# pc_healthypi_move_nRF5340_v4.net
KiCad netlist of a schematic drawn in EAGLE
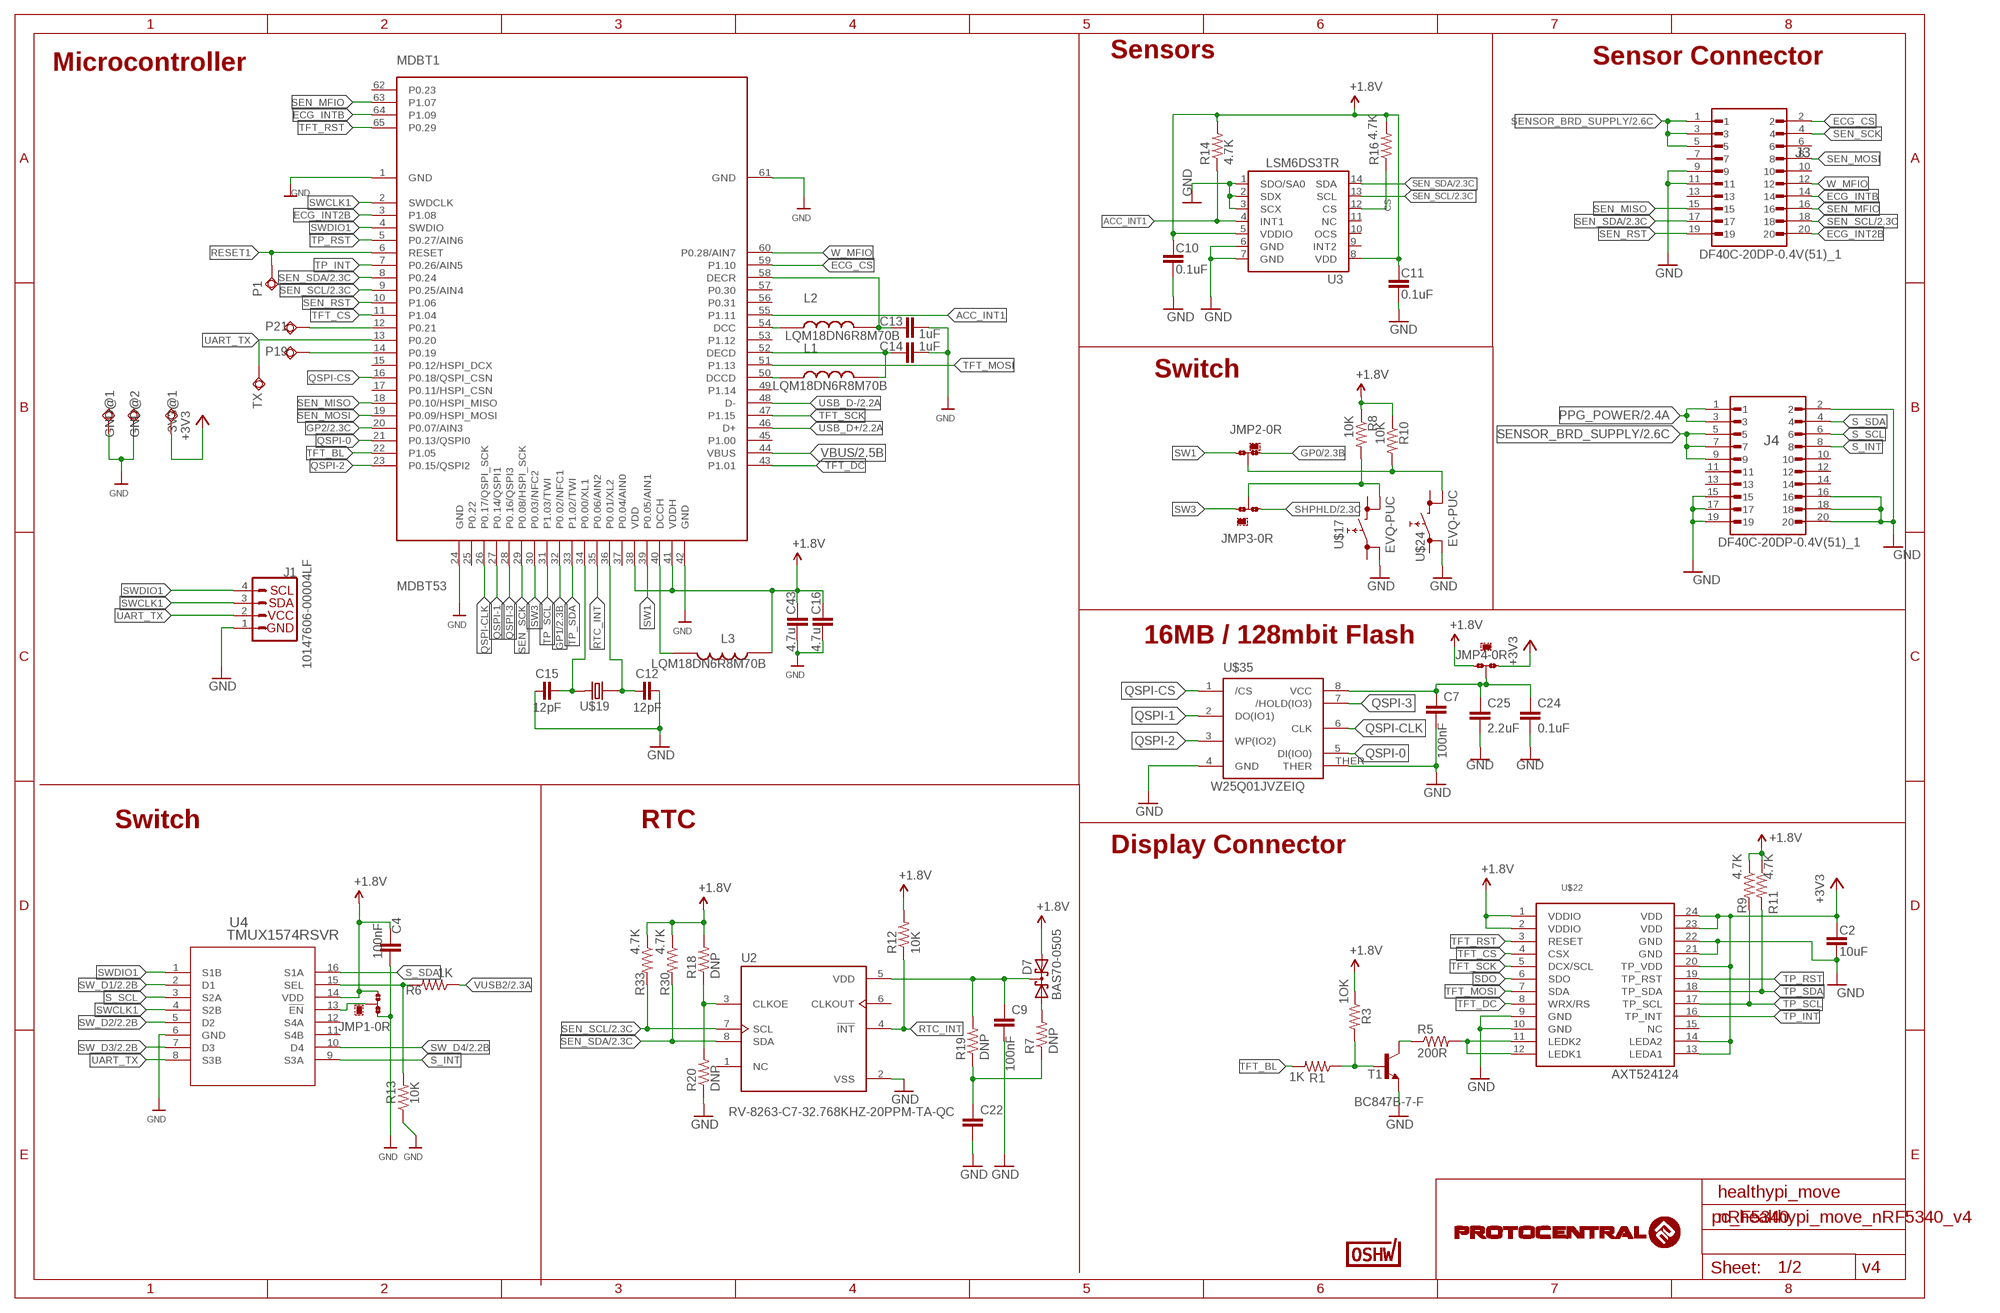
[diagram p0: schematic, sheet 1]
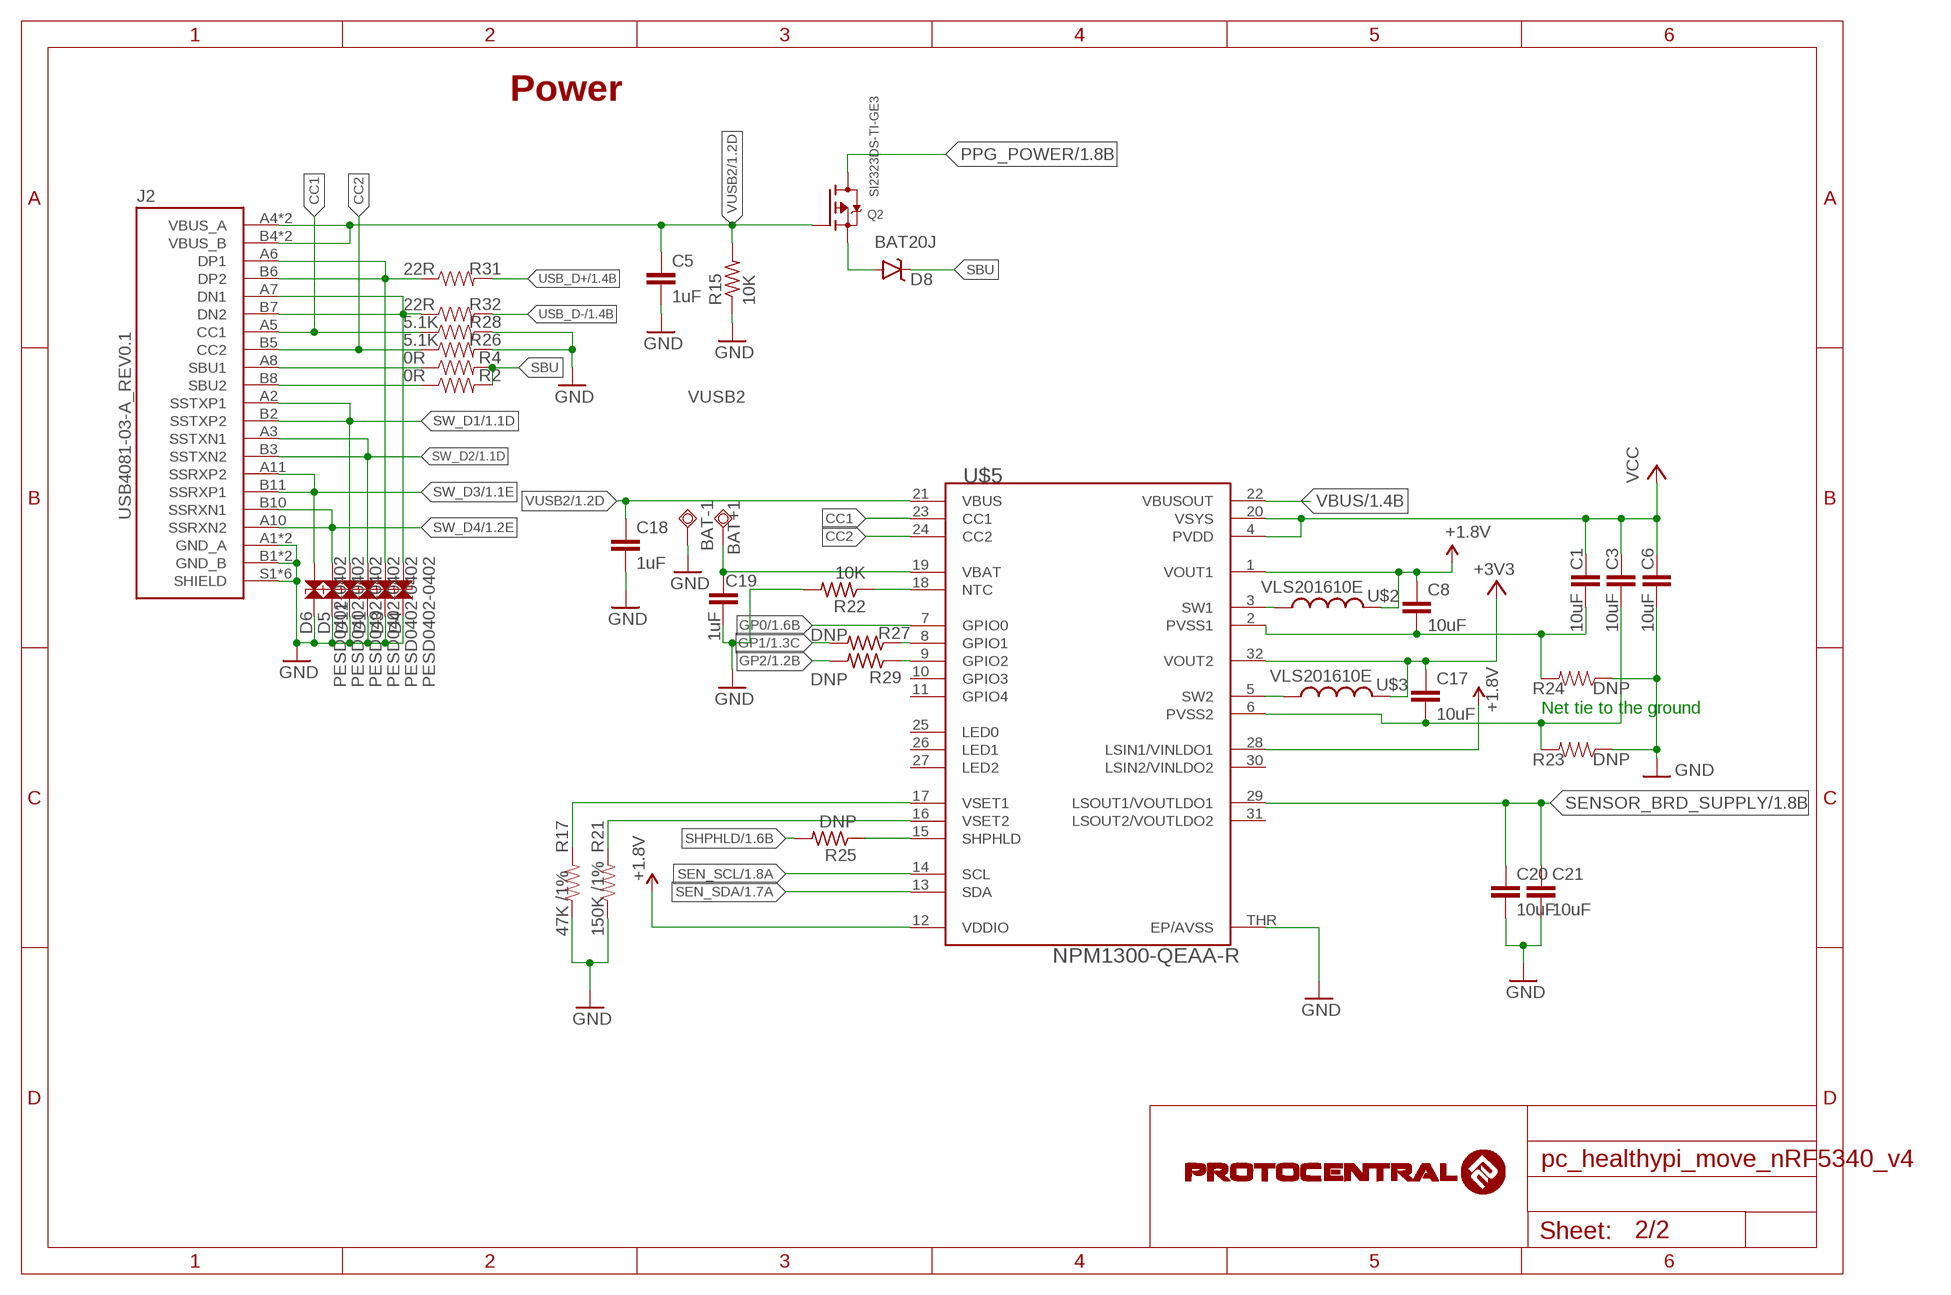
[diagram p1: schematic, sheet 2]

(export (version "E")
  (design (tool "Eeschema 10.0.6"))
  (components
    (comp (ref "BAT+1")
      (value "TPSQTP13SQ")
      (footprint "eagle-import:TP13SQ")
      (libsource (lib "eagle-import") (part "TPSQTP13SQ"))
    )
    (comp (ref "BAT-1")
      (value "TPSQTP13SQ")
      (footprint "eagle-import:TP13SQ")
      (libsource (lib "eagle-import") (part "TPSQTP13SQ"))
    )
    (comp (ref "C1")
      (value "10uF")
      (footprint "eagle-import:0402-TIGHT")
      (libsource (lib "eagle-import") (part "2.2UF-0402_TIGHT-10V-10%-X5R"))
    )
    (comp (ref "C3")
      (value "10uF")
      (footprint "eagle-import:0402-TIGHT")
      (libsource (lib "eagle-import") (part "2.2UF-0402_TIGHT-10V-10%-X5R"))
    )
    (comp (ref "C5")
      (value "1uF")
      (footprint "eagle-import:0402-TIGHT")
      (libsource (lib "eagle-import") (part "2.2UF-0402_TIGHT-10V-10%-X5R"))
    )
    (comp (ref "C6")
      (value "10uF")
      (footprint "eagle-import:0402-TIGHT")
      (libsource (lib "eagle-import") (part "2.2UF-0402_TIGHT-10V-10%-X5R"))
    )
    (comp (ref "C8")
      (value "10uF")
      (footprint "eagle-import:0402-TIGHT")
      (libsource (lib "eagle-import") (part "2.2UF-0402_TIGHT-10V-10%-X5R"))
    )
    (comp (ref "C17")
      (value "10uF")
      (footprint "eagle-import:0402-TIGHT")
      (libsource (lib "eagle-import") (part "2.2UF-0402_TIGHT-10V-10%-X5R"))
    )
    (comp (ref "C18")
      (value "1uF")
      (footprint "eagle-import:0402-TIGHT")
      (libsource (lib "eagle-import") (part "2.2UF-0402_TIGHT-10V-10%-X5R"))
    )
    (comp (ref "C19")
      (value "1uF")
      (footprint "eagle-import:0402-TIGHT")
      (libsource (lib "eagle-import") (part "2.2UF-0402_TIGHT-10V-10%-X5R"))
    )
    (comp (ref "C20")
      (value "10uF")
      (footprint "eagle-import:0402-TIGHT")
      (libsource (lib "eagle-import") (part "2.2UF-0402_TIGHT-10V-10%-X5R"))
    )
    (comp (ref "C21")
      (value "10uF")
      (footprint "eagle-import:0402-TIGHT")
      (libsource (lib "eagle-import") (part "2.2UF-0402_TIGHT-10V-10%-X5R"))
    )
    (comp (ref "D1")
      (value "PESD0402-0402")
      (footprint "eagle-import:0402")
      (fields
        (field (name "DIGIKEY_PART") "PESD0402-140CT-ND")
        (field (name "MOUSE_PART") "650-PESD0402-140")
      )
      (libsource (lib "eagle-import") (part "PESD0402-0402"))
    )
    (comp (ref "D3")
      (value "PESD0402-0402")
      (footprint "eagle-import:0402")
      (fields
        (field (name "DIGIKEY_PART") "PESD0402-140CT-ND")
        (field (name "MOUSE_PART") "650-PESD0402-140")
      )
      (libsource (lib "eagle-import") (part "PESD0402-0402"))
    )
    (comp (ref "D4")
      (value "PESD0402-0402")
      (footprint "eagle-import:0402")
      (fields
        (field (name "DIGIKEY_PART") "PESD0402-140CT-ND")
        (field (name "MOUSE_PART") "650-PESD0402-140")
      )
      (libsource (lib "eagle-import") (part "PESD0402-0402"))
    )
    (comp (ref "D5")
      (value "PESD0402-0402")
      (footprint "eagle-import:0402")
      (fields
        (field (name "DIGIKEY_PART") "PESD0402-140CT-ND")
        (field (name "MOUSE_PART") "650-PESD0402-140")
      )
      (libsource (lib "eagle-import") (part "PESD0402-0402"))
    )
    (comp (ref "D6")
      (value "PESD0402-0402")
      (footprint "eagle-import:0402")
      (fields
        (field (name "DIGIKEY_PART") "PESD0402-140CT-ND")
        (field (name "MOUSE_PART") "650-PESD0402-140")
      )
      (libsource (lib "eagle-import") (part "PESD0402-0402"))
    )
    (comp (ref "D8")
      (value "BAT20J")
      (footprint "eagle-import:SOD-323")
      (libsource (lib "eagle-import") (part "DIODE-SCHOTTKY-BAT20J"))
    )
    (comp (ref "D11")
      (value "PESD0402-0402")
      (footprint "eagle-import:0402")
      (fields
        (field (name "DIGIKEY_PART") "PESD0402-140CT-ND")
        (field (name "MOUSE_PART") "650-PESD0402-140")
      )
      (libsource (lib "eagle-import") (part "PESD0402-0402"))
    )
    (comp (ref "J2")
      (value "USB4081-03-A_REV0.1")
      (footprint "eagle-import:GCT_USB4081-03-A_REV0.1")
      (fields (field (name "MF") "Global Connector Technology") (field (name "MP") "USB4081-03-A"))
      (libsource (lib "eagle-import") (part "USB4081-03-A_REV0.1"))
    )
    (comp (ref "Q2")
      (value "SI2323DS-TI-GE3")
      (footprint "eagle-import:SOT23-R")
      (libsource (lib "eagle-import") (part "MOSFET-P"))
    )
    (comp (ref "R2")
      (value "0R")
      (footprint "eagle-import:0402-RES")
      (libsource (lib "eagle-import") (part "RESISTOR0402-RES"))
    )
    (comp (ref "R4")
      (value "0R")
      (footprint "eagle-import:0402-RES")
      (libsource (lib "eagle-import") (part "RESISTOR0402-RES"))
    )
    (comp (ref "R15")
      (value "10K")
      (footprint "eagle-import:R0402")
      (libsource (lib "eagle-import") (part "R-US_R0402"))
    )
    (comp (ref "R17")
      (value "47K /1%")
      (footprint "eagle-import:0402-RES")
      (libsource (lib "eagle-import") (part "RESISTOR0402-RES"))
    )
    (comp (ref "R21")
      (value "150K /1%")
      (footprint "eagle-import:0402-RES")
      (libsource (lib "eagle-import") (part "RESISTOR0402-RES"))
    )
    (comp (ref "R22")
      (value "10K")
      (footprint "eagle-import:R0402")
      (libsource (lib "eagle-import") (part "R-US_R0402"))
    )
    (comp (ref "R23")
      (value "DNP")
      (footprint "eagle-import:0402-RES")
      (libsource (lib "eagle-import") (part "RESISTOR0402-RES"))
    )
    (comp (ref "R24")
      (value "DNP")
      (footprint "eagle-import:0402-RES")
      (libsource (lib "eagle-import") (part "RESISTOR0402-RES"))
    )
    (comp (ref "R25")
      (value "DNP")
      (footprint "eagle-import:R0402")
      (libsource (lib "eagle-import") (part "R-US_R0402"))
    )
    (comp (ref "R26")
      (value "5.1K")
      (footprint "eagle-import:0402-RES")
      (libsource (lib "eagle-import") (part "RESISTOR0402-RES"))
    )
    (comp (ref "R27")
      (value "DNP")
      (footprint "eagle-import:R0402")
      (libsource (lib "eagle-import") (part "R-US_R0402"))
    )
    (comp (ref "R28")
      (value "5.1K")
      (footprint "eagle-import:0402-RES")
      (libsource (lib "eagle-import") (part "RESISTOR0402-RES"))
    )
    (comp (ref "R29")
      (value "DNP")
      (footprint "eagle-import:R0402")
      (libsource (lib "eagle-import") (part "R-US_R0402"))
    )
    (comp (ref "R31")
      (value "22R")
      (footprint "eagle-import:0402-RES")
      (libsource (lib "eagle-import") (part "RESISTOR0402-RES"))
    )
    (comp (ref "R32")
      (value "22R")
      (footprint "eagle-import:0402-RES")
      (libsource (lib "eagle-import") (part "RESISTOR0402-RES"))
    )
    (comp (ref "U$2")
      (value "VLS201610E")
      (footprint "eagle-import:VLS201610E")
      (libsource (lib "eagle-import") (part "VLS201610E"))
    )
    (comp (ref "U$3")
      (value "VLS201610E")
      (footprint "eagle-import:VLS201610E")
      (libsource (lib "eagle-import") (part "VLS201610E"))
    )
    (comp (ref "U$5")
      (value "NPM1300-QEAA-R")
      (footprint "eagle-import:PWQFN-32")
      (libsource (lib "eagle-import") (part "NPM1300-QEAA-R"))
    )
    (comp (ref "3V3@1")
      (value "TPSQTP13SQ")
      (footprint "eagle-import:TP13SQ")
      (libsource (lib "eagle-import") (part "TPSQTP13SQ"))
    )
    (comp (ref "C2")
      (value "10uF")
      (footprint "eagle-import:0603@1")
      (libsource (lib "eagle-import") (part "0.1UF-0603-100V-10%"))
    )
    (comp (ref "C4")
      (value "100nF")
      (footprint "eagle-import:0402-TIGHT")
      (libsource (lib "eagle-import") (part "2.2UF-0402_TIGHT-10V-10%-X5R"))
    )
    (comp (ref "C7")
      (value "100nF")
      (footprint "eagle-import:C0402")
      (libsource (lib "eagle-import") (part "C-EUC0402"))
    )
    (comp (ref "C9")
      (value "100nF")
      (footprint "eagle-import:C0402")
      (libsource (lib "eagle-import") (part "C-EUC0402"))
    )
    (comp (ref "C10")
      (value "0.1uF")
      (footprint "eagle-import:0402-TIGHT")
      (libsource (lib "eagle-import") (part "0.1UF-0402T-6.3V-10%-X7R"))
    )
    (comp (ref "C11")
      (value "0.1uF")
      (footprint "eagle-import:0402-TIGHT")
      (libsource (lib "eagle-import") (part "0.1UF-0402T-6.3V-10%-X7R"))
    )
    (comp (ref "C12")
      (value "12pF")
      (footprint "eagle-import:C0402")
      (libsource (lib "eagle-import") (part "CAPACITORS-0402"))
    )
    (comp (ref "C13")
      (value "1uF")
      (footprint "eagle-import:0402-TIGHT")
      (libsource (lib "eagle-import") (part "2.2UF-0402_TIGHT-10V-10%-X5R"))
    )
    (comp (ref "C14")
      (value "1uF")
      (footprint "eagle-import:0402-TIGHT")
      (libsource (lib "eagle-import") (part "2.2UF-0402_TIGHT-10V-10%-X5R"))
    )
    (comp (ref "C15")
      (value "12pF")
      (footprint "eagle-import:C0402")
      (libsource (lib "eagle-import") (part "CAPACITORS-0402"))
    )
    (comp (ref "C16")
      (value "4.7u")
      (footprint "eagle-import:C0402")
      (libsource (lib "eagle-import") (part "C-EUC0402"))
    )
    (comp (ref "C22")
      (value "C-EUC1210")
      (footprint "eagle-import:C1210")
      (libsource (lib "eagle-import") (part "C-EUC1210"))
    )
    (comp (ref "C24")
      (value "0.1uF")
      (footprint "eagle-import:0402-TIGHT")
      (libsource (lib "eagle-import") (part "0.1UF-0402T-6.3V-10%-X7R"))
    )
    (comp (ref "C25")
      (value "2.2uF")
      (footprint "eagle-import:0402-TIGHT")
      (libsource (lib "eagle-import") (part "2.2UF-0402_TIGHT-10V-10%-X5R"))
    )
    (comp (ref "C43")
      (value "4.7u")
      (footprint "eagle-import:C0402")
      (libsource (lib "eagle-import") (part "C-EUC0402"))
    )
    (comp (ref "D7")
      (value "BAS70-0505")
      (footprint "eagle-import:SOT23")
      (fields (field (name "MF") "Diotec") (field (name "MP") "BAS70-05"))
      (libsource (lib "eagle-import") (part "BAS70-0505"))
    )
    (comp (ref "GND@1")
      (value "TPSQTP13SQ")
      (footprint "eagle-import:TP13SQ")
      (libsource (lib "eagle-import") (part "TPSQTP13SQ"))
    )
    (comp (ref "GND@2")
      (value "TPSQTP13SQ")
      (footprint "eagle-import:TP13SQ")
      (libsource (lib "eagle-import") (part "TPSQTP13SQ"))
    )
    (comp (ref "J1")
      (value "10147606-00004LF")
      (footprint "eagle-import:JST04_1MM_RA")
      (libsource (lib "eagle-import") (part "QWIIC_CONNECTORJS-1MM"))
    )
    (comp (ref "J3")
      (value "DF40C-20DP-0.4V(51)_1")
      (footprint "eagle-import:HRS_DF40C-20DP-0.4V(51)")
      (fields (field (name "MANUFACTURER") "Hirose Electric"))
      (libsource (lib "eagle-import") (part "DF40C-20DP-0.4V(51)_1"))
    )
    (comp (ref "J4")
      (value "DF40C-20DP-0.4V(51)_1")
      (footprint "eagle-import:HRS_DF40C-20DP-0.4V(51)")
      (fields (field (name "MANUFACTURER") "Hirose Electric"))
      (libsource (lib "eagle-import") (part "DF40C-20DP-0.4V(51)_1"))
    )
    (comp (ref "JMP1")
      (value "0R-JUMPB")
      (footprint "eagle-import:B0R-JMP")
      (libsource (lib "eagle-import") (part "0R-JUMPB"))
    )
    (comp (ref "JMP2")
      (value "0R-JUMPB")
      (footprint "eagle-import:B0R-JMP")
      (libsource (lib "eagle-import") (part "0R-JUMPB"))
    )
    (comp (ref "JMP3")
      (value "0R-JUMPB")
      (footprint "eagle-import:B0R-JMP")
      (libsource (lib "eagle-import") (part "0R-JUMPB"))
    )
    (comp (ref "JMP4")
      (value "0R-JUMPB")
      (footprint "eagle-import:B0R-JMP")
      (libsource (lib "eagle-import") (part "0R-JUMPB"))
    )
    (comp (ref "L1")
      (value "LQM18DN6R8M70B")
      (footprint "eagle-import:INDC1608X95N")
      (fields (field (name "MF") "Murata"))
      (libsource (lib "eagle-import") (part "LQM18DN6R8M70B"))
    )
    (comp (ref "L2")
      (value "LQM18DN6R8M70B")
      (footprint "eagle-import:INDC1608X95N")
      (fields (field (name "MF") "Murata"))
      (libsource (lib "eagle-import") (part "LQM18DN6R8M70B"))
    )
    (comp (ref "L3")
      (value "LQM18DN6R8M70B")
      (footprint "eagle-import:INDC1608X95N")
      (fields (field (name "MF") "Murata"))
      (libsource (lib "eagle-import") (part "LQM18DN6R8M70B"))
    )
    (comp (ref "MDBT1")
      (value "MDBT53")
      (footprint "eagle-import:MDBT53")
      (libsource (lib "eagle-import") (part "MDBT53"))
    )
    (comp (ref "P1")
      (value "TPSQTP13SQ")
      (footprint "eagle-import:TP13SQ")
      (libsource (lib "eagle-import") (part "TPSQTP13SQ"))
    )
    (comp (ref "P19")
      (value "TPSQTP13SQ")
      (footprint "eagle-import:TP13SQ")
      (libsource (lib "eagle-import") (part "TPSQTP13SQ"))
    )
    (comp (ref "P21")
      (value "TPSQTP13SQ")
      (footprint "eagle-import:TP13SQ")
      (libsource (lib "eagle-import") (part "TPSQTP13SQ"))
    )
    (comp (ref "R1")
      (value "200")
      (footprint "eagle-import:R0402")
      (libsource (lib "eagle-import") (part "R-US_R0402"))
    )
    (comp (ref "R3")
      (value "200")
      (footprint "eagle-import:R0402")
      (libsource (lib "eagle-import") (part "R-US_R0402"))
    )
    (comp (ref "R5")
      (value "200R")
      (footprint "eagle-import:R0402")
      (libsource (lib "eagle-import") (part "R-US_R0402"))
    )
    (comp (ref "R6")
      (value "1K")
      (footprint "eagle-import:0402-RES")
      (libsource (lib "eagle-import") (part "RESISTOR0402-RES"))
    )
    (comp (ref "R7")
      (value "DNP")
      (footprint "eagle-import:R0402")
      (libsource (lib "eagle-import") (part "R-US_R0402"))
    )
    (comp (ref "R8")
      (value "10K")
      (footprint "eagle-import:R0402")
      (libsource (lib "eagle-import") (part "R-US_R0402"))
    )
    (comp (ref "R9")
      (value "4.7K")
      (footprint "eagle-import:R0402")
      (libsource (lib "eagle-import") (part "R-US_R0402"))
    )
    (comp (ref "R10")
      (value "10K")
      (footprint "eagle-import:R0402")
      (libsource (lib "eagle-import") (part "R-US_R0402"))
    )
    (comp (ref "R11")
      (value "4.7K")
      (footprint "eagle-import:R0402")
      (libsource (lib "eagle-import") (part "R-US_R0402"))
    )
    (comp (ref "R12")
      (value "10K")
      (footprint "eagle-import:R0402")
      (libsource (lib "eagle-import") (part "R-US_R0402"))
    )
    (comp (ref "R13")
      (value "10K")
      (footprint "eagle-import:R0402")
      (libsource (lib "eagle-import") (part "R-US_R0402"))
    )
    (comp (ref "R14")
      (value "4.7K")
      (footprint "eagle-import:R0402")
      (libsource (lib "eagle-import") (part "R-US_R0402"))
    )
    (comp (ref "R16")
      (value "4.7K")
      (footprint "eagle-import:R0402")
      (libsource (lib "eagle-import") (part "R-US_R0402"))
    )
    (comp (ref "R18")
      (value "DNP")
      (footprint "eagle-import:R0402")
      (libsource (lib "eagle-import") (part "R-US_R0402"))
    )
    (comp (ref "R19")
      (value "DNP")
      (footprint "eagle-import:R0402")
      (libsource (lib "eagle-import") (part "R-US_R0402"))
    )
    (comp (ref "R20")
      (value "DNP")
      (footprint "eagle-import:R0402")
      (libsource (lib "eagle-import") (part "R-US_R0402"))
    )
    (comp (ref "R30")
      (value "4.7K")
      (footprint "eagle-import:R0402")
      (libsource (lib "eagle-import") (part "R-US_R0402"))
    )
    (comp (ref "R33")
      (value "4.7K")
      (footprint "eagle-import:R0402")
      (libsource (lib "eagle-import") (part "R-US_R0402"))
    )
    (comp (ref "T1")
      (value "BC847B-7-F")
      (footprint "eagle-import:SOT23-BEC")
      (libsource (lib "eagle-import") (part "-NPN-SOT23-BECMMBT2222ALT1"))
    )
    (comp (ref "TX")
      (value "TPSQTP13SQ")
      (footprint "eagle-import:TP13SQ")
      (libsource (lib "eagle-import") (part "TPSQTP13SQ"))
    )
    (comp (ref "U$1")
      (value "CERT-SMALL")
      (footprint "eagle-import:CERT-SMALL-SILK")
      (libsource (lib "eagle-import") (part "CERT-SMALL"))
    )
    (comp (ref "U$17")
      (value "EVQ-PUC")
      (footprint "eagle-import:EVQ-PUC")
      (libsource (lib "eagle-import") (part "EVQ-PUC"))
    )
    (comp (ref "U$19")
      (value "520-327-12.5-34B(32.768KHZ)")
      (footprint "eagle-import:ECX-31B")
      (libsource (lib "eagle-import") (part "ECS-X-34B"))
    )
    (comp (ref "U$22")
      (value "AXT524124")
      (footprint "eagle-import:AXT524124")
      (libsource (lib "eagle-import") (part "AXT524124"))
    )
    (comp (ref "U$24")
      (value "EVQ-PUC")
      (footprint "eagle-import:EVQ-PUC")
      (libsource (lib "eagle-import") (part "EVQ-PUC"))
    )
    (comp (ref "U$35")
      (value "W25Q01JVZEIQ")
      (footprint "eagle-import:WSON-08")
      (libsource (lib "eagle-import") (part "W25N01GVZEIG"))
    )
    (comp (ref "U2")
      (value "RV-8263-C7-32.768KHZ-20PPM-TA-QC")
      (footprint "eagle-import:IC_RV-8263-C7-32.768KHZ-20PPM-TA-QC")
      (fields (field (name "MF") "Micro Crystal"))
      (libsource (lib "eagle-import") (part "RV-8263-C7-32.768KHZ-20PPM-TA-QC"))
    )
    (comp (ref "U3")
      (value "LSM6DS3TR")
      (footprint "eagle-import:LGA14L")
      (libsource (lib "eagle-import") (part "LSM6DS3"))
    )
    (comp (ref "U4")
      (value "TMUX1574RSVR")
      (footprint "eagle-import:RSV16_TEX")
      (fields (field (name "COPYRIGHT") "Copyright (C) 2024 Ultra Librarian. All rights reserved."))
      (libsource (lib "eagle-import") (part "TMUX1574RSVR"))
    )
  )
  (nets
    (net (code "1") (name "+1.8V") (class "Default")
      (node (ref "C10") (pin "1") (pinfunction "1_1") (pintype "passive"))
      (node (ref "C11") (pin "1") (pinfunction "1_1") (pintype "passive"))
      (node (ref "C16") (pin "1") (pinfunction "1_1") (pintype "passive"))
      (node (ref "C4") (pin "1") (pinfunction "1_1") (pintype "passive"))
      (node (ref "C43") (pin "1") (pinfunction "1_1") (pintype "passive"))
      (node (ref "C8") (pin "1") (pinfunction "1_1") (pintype "passive"))
      (node (ref "D7") (pin "2") (pinfunction "A2_2") (pintype "passive"))
      (node (ref "JMP1") (pin "3") (pinfunction "3_3") (pintype "passive"))
      (node (ref "JMP4") (pin "3") (pinfunction "3_3") (pintype "passive"))
      (node (ref "L3") (pin "1") (pinfunction "1_1") (pintype "passive"))
      (node (ref "MDBT1") (pin "38") (pinfunction "VDD_38") (pintype "bidirectional"))
      (node (ref "MDBT1") (pin "41") (pinfunction "VDDH_41") (pintype "bidirectional"))
      (node (ref "R10") (pin "1") (pinfunction "1_1") (pintype "passive"))
      (node (ref "R11") (pin "1") (pinfunction "1_1") (pintype "passive"))
      (node (ref "R12") (pin "2") (pinfunction "2_2") (pintype "passive"))
      (node (ref "R14") (pin "2") (pinfunction "2_2") (pintype "passive"))
      (node (ref "R16") (pin "2") (pinfunction "2_2") (pintype "passive"))
      (node (ref "R18") (pin "2") (pinfunction "2_2") (pintype "passive"))
      (node (ref "R3") (pin "1") (pinfunction "1_1") (pintype "passive"))
      (node (ref "R30") (pin "1") (pinfunction "1_1") (pintype "passive"))
      (node (ref "R33") (pin "1") (pinfunction "1_1") (pintype "passive"))
      (node (ref "R8") (pin "1") (pinfunction "1_1") (pintype "passive"))
      (node (ref "R9") (pin "1") (pinfunction "1_1") (pintype "passive"))
      (node (ref "U$2") (pin "2") (pinfunction "2_2") (pintype "passive"))
      (node (ref "U$22") (pin "1") (pinfunction "VDDIO_1") (pintype "bidirectional"))
      (node (ref "U$22") (pin "2") (pinfunction "VDDIO_2") (pintype "bidirectional"))
      (node (ref "U$5") (pin "1") (pinfunction "VOUT1_1") (pintype "bidirectional"))
      (node (ref "U$5") (pin "12") (pinfunction "VDDIO_12") (pintype "bidirectional"))
      (node (ref "U$5") (pin "28") (pinfunction "LSIN1/VINLDO1_28") (pintype "bidirectional"))
      (node (ref "U3") (pin "5") (pinfunction "VDDIO_5") (pintype "bidirectional"))
      (node (ref "U3") (pin "8") (pinfunction "VDD_8") (pintype "bidirectional"))
      (node (ref "U4") (pin "14") (pinfunction "VDD_14") (pintype "power_in"))
    )
    (net (code "2") (name "+3V3") (class "Default")
      (node (ref "3V3@1") (pin "TP") (pinfunction "TP_TP") (pintype "input"))
      (node (ref "C17") (pin "1") (pinfunction "1_1") (pintype "passive"))
      (node (ref "C2") (pin "1") (pinfunction "1_1") (pintype "passive"))
      (node (ref "JMP4") (pin "1") (pinfunction "1_1") (pintype "passive"))
      (node (ref "U$22") (pin "13") (pinfunction "LEDA1_13") (pintype "bidirectional"))
      (node (ref "U$22") (pin "14") (pinfunction "LEDA2_14") (pintype "bidirectional"))
      (node (ref "U$22") (pin "20") (pinfunction "TP_VDD_20") (pintype "bidirectional"))
      (node (ref "U$22") (pin "23") (pinfunction "VDD_23") (pintype "bidirectional"))
      (node (ref "U$22") (pin "24") (pinfunction "VDD_24") (pintype "bidirectional"))
      (node (ref "U$3") (pin "2") (pinfunction "2_2") (pintype "passive"))
      (node (ref "U$5") (pin "32") (pinfunction "VOUT2_32") (pintype "bidirectional"))
    )
    (net (code "3") (name "ACC_INT1") (class "Default")
      (node (ref "MDBT1") (pin "55") (pinfunction "P1.11_55") (pintype "bidirectional"))
      (node (ref "R14") (pin "1") (pinfunction "1_1") (pintype "passive"))
      (node (ref "U3") (pin "4") (pinfunction "INT1_4") (pintype "bidirectional"))
    )
    (net (code "4") (name "CC1") (class "Default")
      (node (ref "J2") (pin "A5") (pinfunction "CC1_A5") (pintype "bidirectional"))
      (node (ref "R28") (pin "1") (pinfunction "1_1") (pintype "passive"))
      (node (ref "U$5") (pin "23") (pinfunction "CC1_23") (pintype "bidirectional"))
    )
    (net (code "5") (name "CC2") (class "Default")
      (node (ref "J2") (pin "B5") (pinfunction "CC2_B5") (pintype "bidirectional"))
      (node (ref "R26") (pin "1") (pinfunction "1_1") (pintype "passive"))
      (node (ref "U$5") (pin "24") (pinfunction "CC2_24") (pintype "bidirectional"))
    )
    (net (code "6") (name "CS") (class "Default")
      (node (ref "R16") (pin "1") (pinfunction "1_1") (pintype "passive"))
      (node (ref "U3") (pin "12") (pinfunction "CS_12") (pintype "bidirectional"))
    )
    (net (code "7") (name "ECG_CS") (class "Default")
      (node (ref "J3") (pin "2") (pinfunction "2_2") (pintype "passive"))
      (node (ref "MDBT1") (pin "59") (pinfunction "P1.10_59") (pintype "bidirectional"))
    )
    (net (code "8") (name "ECG_INT2B") (class "Default")
      (node (ref "J3") (pin "20") (pinfunction "20_20") (pintype "passive"))
      (node (ref "MDBT1") (pin "3") (pinfunction "P1.08_3") (pintype "bidirectional"))
    )
    (net (code "9") (name "ECG_INTB") (class "Default")
      (node (ref "J3") (pin "14") (pinfunction "14_14") (pintype "passive"))
      (node (ref "MDBT1") (pin "64") (pinfunction "P1.09_64") (pintype "bidirectional"))
    )
    (net (code "10") (name "GND") (class "Default")
      (node (ref "BAT-1") (pin "TP") (pinfunction "TP_TP") (pintype "input"))
      (node (ref "C10") (pin "2") (pinfunction "2_2") (pintype "passive"))
      (node (ref "C11") (pin "2") (pinfunction "2_2") (pintype "passive"))
      (node (ref "C12") (pin "2") (pinfunction "2_2") (pintype "passive"))
      (node (ref "C13") (pin "2") (pinfunction "2_2") (pintype "passive"))
      (node (ref "C14") (pin "2") (pinfunction "2_2") (pintype "passive"))
      (node (ref "C15") (pin "1") (pinfunction "1_1") (pintype "passive"))
      (node (ref "C16") (pin "2") (pinfunction "2_2") (pintype "passive"))
      (node (ref "C18") (pin "2") (pinfunction "2_2") (pintype "passive"))
      (node (ref "C19") (pin "2") (pinfunction "2_2") (pintype "passive"))
      (node (ref "C2") (pin "2") (pinfunction "2_2") (pintype "passive"))
      (node (ref "C20") (pin "2") (pinfunction "2_2") (pintype "passive"))
      (node (ref "C21") (pin "2") (pinfunction "2_2") (pintype "passive"))
      (node (ref "C22") (pin "2") (pinfunction "2_2") (pintype "passive"))
      (node (ref "C24") (pin "2") (pinfunction "2_2") (pintype "passive"))
      (node (ref "C25") (pin "2") (pinfunction "2_2") (pintype "passive"))
      (node (ref "C4") (pin "2") (pinfunction "2_2") (pintype "passive"))
      (node (ref "C43") (pin "2") (pinfunction "2_2") (pintype "passive"))
      (node (ref "C5") (pin "2") (pinfunction "2_2") (pintype "passive"))
      (node (ref "C6") (pin "2") (pinfunction "2_2") (pintype "passive"))
      (node (ref "C7") (pin "2") (pinfunction "2_2") (pintype "passive"))
      (node (ref "C9") (pin "2") (pinfunction "2_2") (pintype "passive"))
      (node (ref "D1") (pin "1") (pinfunction "1_1") (pintype "bidirectional"))
      (node (ref "D11") (pin "1") (pinfunction "1_1") (pintype "bidirectional"))
      (node (ref "D3") (pin "1") (pinfunction "1_1") (pintype "bidirectional"))
      (node (ref "D4") (pin "1") (pinfunction "1_1") (pintype "bidirectional"))
      (node (ref "D5") (pin "1") (pinfunction "1_1") (pintype "bidirectional"))
      (node (ref "D6") (pin "1") (pinfunction "1_1") (pintype "bidirectional"))
      (node (ref "GND@1") (pin "TP") (pinfunction "TP_TP") (pintype "input"))
      (node (ref "GND@2") (pin "TP") (pinfunction "TP_TP") (pintype "input"))
      (node (ref "J1") (pin "1") (pinfunction "1_1") (pintype "power_in"))
      (node (ref "J2") (pin "A1") (pinfunction "GND_A_A1") (pintype "power_in"))
      (node (ref "J2") (pin "A12") (pinfunction "GND_A_A12") (pintype "power_in"))
      (node (ref "J2") (pin "B1") (pinfunction "GND_B_B1") (pintype "power_in"))
      (node (ref "J2") (pin "B12") (pinfunction "GND_B_B12") (pintype "power_in"))
      (node (ref "J2") (pin "S1") (pinfunction "SHIELD_S1") (pintype "passive"))
      (node (ref "J2") (pin "S2") (pinfunction "SHIELD_S2") (pintype "passive"))
      (node (ref "J2") (pin "S3") (pinfunction "SHIELD_S3") (pintype "passive"))
      (node (ref "J2") (pin "S4") (pinfunction "SHIELD_S4") (pintype "passive"))
      (node (ref "J2") (pin "S5") (pinfunction "SHIELD_S5") (pintype "passive"))
      (node (ref "J2") (pin "S6") (pinfunction "SHIELD_S6") (pintype "passive"))
      (node (ref "J3") (pin "11") (pinfunction "11_11") (pintype "passive"))
      (node (ref "J3") (pin "9") (pinfunction "9_9") (pintype "passive"))
      (node (ref "J4") (pin "15") (pinfunction "15_15") (pintype "passive"))
      (node (ref "J4") (pin "16") (pinfunction "16_16") (pintype "passive"))
      (node (ref "J4") (pin "17") (pinfunction "17_17") (pintype "passive"))
      (node (ref "J4") (pin "18") (pinfunction "18_18") (pintype "passive"))
      (node (ref "J4") (pin "19") (pinfunction "19_19") (pintype "passive"))
      (node (ref "J4") (pin "2") (pinfunction "2_2") (pintype "passive"))
      (node (ref "J4") (pin "20") (pinfunction "20_20") (pintype "passive"))
      (node (ref "JMP1") (pin "1") (pinfunction "1_1") (pintype "passive"))
      (node (ref "MDBT1") (pin "1") (pinfunction "GND_1") (pintype "bidirectional"))
      (node (ref "MDBT1") (pin "24") (pinfunction "GND_24") (pintype "bidirectional"))
      (node (ref "MDBT1") (pin "42") (pinfunction "GND_42") (pintype "bidirectional"))
      (node (ref "MDBT1") (pin "61") (pinfunction "GND_61") (pintype "bidirectional"))
      (node (ref "R13") (pin "1") (pinfunction "1_1") (pintype "passive"))
      (node (ref "R15") (pin "1") (pinfunction "1_1") (pintype "passive"))
      (node (ref "R17") (pin "1") (pinfunction "1_1") (pintype "passive"))
      (node (ref "R20") (pin "1") (pinfunction "1_1") (pintype "passive"))
      (node (ref "R21") (pin "1") (pinfunction "1_1") (pintype "passive"))
      (node (ref "R22") (pin "2") (pinfunction "2_2") (pintype "passive"))
      (node (ref "R23") (pin "1") (pinfunction "1_1") (pintype "passive"))
      (node (ref "R24") (pin "1") (pinfunction "1_1") (pintype "passive"))
      (node (ref "R26") (pin "2") (pinfunction "2_2") (pintype "passive"))
      (node (ref "R28") (pin "2") (pinfunction "2_2") (pintype "passive"))
      (node (ref "T1") (pin "E") (pinfunction "E_E") (pintype "passive"))
      (node (ref "U$17") (pin "3") (pinfunction "0_3") (pintype "passive"))
      (node (ref "U$22") (pin "10") (pinfunction "GND_10") (pintype "bidirectional"))
      (node (ref "U$22") (pin "21") (pinfunction "GND_21") (pintype "bidirectional"))
      (node (ref "U$22") (pin "22") (pinfunction "GND_22") (pintype "bidirectional"))
      (node (ref "U$22") (pin "9") (pinfunction "GND_9") (pintype "bidirectional"))
      (node (ref "U$24") (pin "3") (pinfunction "0_3") (pintype "passive"))
      (node (ref "U$35") (pin "4") (pinfunction "GND_4") (pintype "bidirectional"))
      (node (ref "U$35") (pin "THER") (pinfunction "THER_THER") (pintype "bidirectional"))
      (node (ref "U$5") (pin "THR") (pinfunction "EP/AVSS_THR") (pintype "bidirectional"))
      (node (ref "U2") (pin "2") (pinfunction "VSS_2") (pintype "power_in"))
      (node (ref "U3") (pin "1") (pinfunction "SDO/SA0_1") (pintype "bidirectional"))
      (node (ref "U3") (pin "2") (pinfunction "SDX_2") (pintype "bidirectional"))
      (node (ref "U3") (pin "3") (pinfunction "SCX_3") (pintype "bidirectional"))
      (node (ref "U3") (pin "6") (pinfunction "GND_6") (pintype "bidirectional"))
      (node (ref "U3") (pin "7") (pinfunction "GND_7") (pintype "bidirectional"))
      (node (ref "U4") (pin "6") (pinfunction "GND_6") (pintype "passive"))
    )
    (net (code "11") (name "GP0") (class "Default")
      (node (ref "JMP2") (pin "1") (pinfunction "1_1") (pintype "passive"))
      (node (ref "U$5") (pin "7") (pinfunction "GPIO0_7") (pintype "bidirectional"))
    )
    (net (code "12") (name "GP1") (class "Default")
      (node (ref "MDBT1") (pin "32") (pinfunction "P0.02/NFC1_32") (pintype "bidirectional"))
      (node (ref "R27") (pin "2") (pinfunction "2_2") (pintype "passive"))
    )
    (net (code "13") (name "GP2") (class "Default")
      (node (ref "MDBT1") (pin "20") (pinfunction "P0.07/AIN3_20") (pintype "bidirectional"))
      (node (ref "R29") (pin "2") (pinfunction "2_2") (pintype "passive"))
    )
    (net (code "14") (name "Net-(C22-Pad1)") (class "Default")
      (node (ref "C22") (pin "1") (pinfunction "1_1") (pintype "passive"))
      (node (ref "R19") (pin "1") (pinfunction "1_1") (pintype "passive"))
      (node (ref "R7") (pin "1") (pinfunction "1_1") (pintype "passive"))
    )
    (net (code "15") (name "Net-(D7-A1)") (class "Default")
      (node (ref "D7") (pin "1") (pinfunction "A1_1") (pintype "passive"))
      (node (ref "R7") (pin "2") (pinfunction "2_2") (pintype "passive"))
    )
    (net (code "16") (name "Net-(D7-K1K2)") (class "Default")
      (node (ref "C9") (pin "1") (pinfunction "1_1") (pintype "passive"))
      (node (ref "D7") (pin "3") (pinfunction "K1K2_3") (pintype "passive"))
      (node (ref "R19") (pin "2") (pinfunction "2_2") (pintype "passive"))
      (node (ref "U2") (pin "5") (pinfunction "VDD_5") (pintype "power_in"))
    )
    (net (code "17") (name "Net-(J2-DN1)") (class "Default")
      (node (ref "D4") (pin "2") (pinfunction "2_2") (pintype "bidirectional"))
      (node (ref "J2") (pin "A7") (pinfunction "DN1_A7") (pintype "bidirectional"))
      (node (ref "J2") (pin "B7") (pinfunction "DN2_B7") (pintype "bidirectional"))
      (node (ref "R32") (pin "1") (pinfunction "1_1") (pintype "passive"))
    )
    (net (code "18") (name "Net-(J2-DP1)") (class "Default")
      (node (ref "D3") (pin "2") (pinfunction "2_2") (pintype "bidirectional"))
      (node (ref "J2") (pin "A6") (pinfunction "DP1_A6") (pintype "bidirectional"))
      (node (ref "J2") (pin "B6") (pinfunction "DP2_B6") (pintype "bidirectional"))
      (node (ref "R31") (pin "1") (pinfunction "1_1") (pintype "passive"))
    )
    (net (code "19") (name "Net-(J2-SBU1)") (class "Default")
      (node (ref "J2") (pin "A8") (pinfunction "SBU1_A8") (pintype "bidirectional"))
      (node (ref "R4") (pin "1") (pinfunction "1_1") (pintype "passive"))
    )
    (net (code "20") (name "Net-(J2-SBU2)") (class "Default")
      (node (ref "J2") (pin "B8") (pinfunction "SBU2_B8") (pintype "bidirectional"))
      (node (ref "R2") (pin "1") (pinfunction "1_1") (pintype "passive"))
    )
    (net (code "21") (name "Net-(JMP2-Pad2)") (class "Default")
      (node (ref "JMP2") (pin "2") (pinfunction "2_2") (pintype "passive"))
      (node (ref "R10") (pin "2") (pinfunction "2_2") (pintype "passive"))
      (node (ref "U$24") (pin "2") (pinfunction "1_2") (pintype "passive"))
    )
    (net (code "22") (name "Net-(JMP3-Pad2)") (class "Default")
      (node (ref "JMP3") (pin "2") (pinfunction "2_2") (pintype "passive"))
      (node (ref "R8") (pin "2") (pinfunction "2_2") (pintype "passive"))
      (node (ref "U$17") (pin "2") (pinfunction "1_2") (pintype "passive"))
    )
    (net (code "23") (name "Net-(MDBT1-DCC)") (class "Default")
      (node (ref "L2") (pin "1") (pinfunction "1_1") (pintype "passive"))
      (node (ref "MDBT1") (pin "54") (pinfunction "DCC_54") (pintype "bidirectional"))
    )
    (net (code "24") (name "Net-(MDBT1-DCCD)") (class "Default")
      (node (ref "L1") (pin "1") (pinfunction "1_1") (pintype "passive"))
      (node (ref "MDBT1") (pin "50") (pinfunction "DCCD_50") (pintype "bidirectional"))
    )
    (net (code "25") (name "Net-(MDBT1-DCCH)") (class "Default")
      (node (ref "L3") (pin "2") (pinfunction "2_2") (pintype "passive"))
      (node (ref "MDBT1") (pin "40") (pinfunction "DCCH_40") (pintype "bidirectional"))
    )
    (net (code "26") (name "Net-(MDBT1-DECD)") (class "Default")
      (node (ref "C14") (pin "1") (pinfunction "1_1") (pintype "passive"))
      (node (ref "L1") (pin "2") (pinfunction "2_2") (pintype "passive"))
      (node (ref "MDBT1") (pin "52") (pinfunction "DECD_52") (pintype "bidirectional"))
    )
    (net (code "27") (name "Net-(MDBT1-DECR)") (class "Default")
      (node (ref "C13") (pin "1") (pinfunction "1_1") (pintype "passive"))
      (node (ref "L2") (pin "2") (pinfunction "2_2") (pintype "passive"))
      (node (ref "MDBT1") (pin "58") (pinfunction "DECR_58") (pintype "bidirectional"))
    )
    (net (code "28") (name "Net-(MDBT1-P0.00{slash}XL1)") (class "Default")
      (node (ref "C15") (pin "2") (pinfunction "2_2") (pintype "passive"))
      (node (ref "MDBT1") (pin "34") (pinfunction "P0.00/XL1_34") (pintype "bidirectional"))
      (node (ref "U$19") (pin "P$2") (pinfunction "2_P$2") (pintype "passive"))
    )
    (net (code "29") (name "Net-(MDBT1-P0.01{slash}XL2)") (class "Default")
      (node (ref "C12") (pin "1") (pinfunction "1_1") (pintype "passive"))
      (node (ref "MDBT1") (pin "36") (pinfunction "P0.01/XL2_36") (pintype "bidirectional"))
      (node (ref "U$19") (pin "P$1") (pinfunction "1_P$1") (pintype "passive"))
    )
    (net (code "30") (name "Net-(MDBT1-P0.19)") (class "Default")
      (node (ref "MDBT1") (pin "14") (pinfunction "P0.19_14") (pintype "bidirectional"))
      (node (ref "P19") (pin "TP") (pinfunction "TP_TP") (pintype "input"))
    )
    (net (code "31") (name "Net-(MDBT1-P0.21)") (class "Default")
      (node (ref "MDBT1") (pin "12") (pinfunction "P0.21_12") (pintype "bidirectional"))
      (node (ref "P21") (pin "TP") (pinfunction "TP_TP") (pintype "input"))
    )
    (net (code "32") (name "Net-(Q2-S)") (class "Default")
      (node (ref "D8") (pin "A") (pinfunction "A_A") (pintype "passive"))
      (node (ref "Q2") (pin "2") (pinfunction "S_2") (pintype "passive"))
    )
    (net (code "33") (name "Net-(R1-Pad1)") (class "Default")
      (node (ref "R1") (pin "1") (pinfunction "1_1") (pintype "passive"))
      (node (ref "R3") (pin "2") (pinfunction "2_2") (pintype "passive"))
      (node (ref "T1") (pin "B") (pinfunction "B_B") (pintype "passive"))
    )
    (net (code "34") (name "Net-(R5-Pad1)") (class "Default")
      (node (ref "R5") (pin "1") (pinfunction "1_1") (pintype "passive"))
      (node (ref "T1") (pin "C") (pinfunction "C_C") (pintype "passive"))
    )
    (net (code "35") (name "Net-(U$5-GPIO1)") (class "Default")
      (node (ref "R27") (pin "1") (pinfunction "1_1") (pintype "passive"))
      (node (ref "U$5") (pin "8") (pinfunction "GPIO1_8") (pintype "bidirectional"))
    )
    (net (code "36") (name "Net-(U$5-GPIO2)") (class "Default")
      (node (ref "R29") (pin "1") (pinfunction "1_1") (pintype "passive"))
      (node (ref "U$5") (pin "9") (pinfunction "GPIO2_9") (pintype "bidirectional"))
    )
    (net (code "37") (name "Net-(U$5-NTC)") (class "Default")
      (node (ref "R22") (pin "1") (pinfunction "1_1") (pintype "passive"))
      (node (ref "U$5") (pin "18") (pinfunction "NTC_18") (pintype "bidirectional"))
    )
    (net (code "38") (name "Net-(U$5-PVSS1)") (class "Default")
      (node (ref "C1") (pin "2") (pinfunction "2_2") (pintype "passive"))
      (node (ref "C8") (pin "2") (pinfunction "2_2") (pintype "passive"))
      (node (ref "R24") (pin "2") (pinfunction "2_2") (pintype "passive"))
      (node (ref "U$5") (pin "2") (pinfunction "PVSS1_2") (pintype "bidirectional"))
    )
    (net (code "39") (name "Net-(U$5-PVSS2)") (class "Default")
      (node (ref "C17") (pin "2") (pinfunction "2_2") (pintype "passive"))
      (node (ref "C3") (pin "2") (pinfunction "2_2") (pintype "passive"))
      (node (ref "R23") (pin "2") (pinfunction "2_2") (pintype "passive"))
      (node (ref "U$5") (pin "6") (pinfunction "PVSS2_6") (pintype "bidirectional"))
    )
    (net (code "40") (name "Net-(U$5-SHPHLD)") (class "Default")
      (node (ref "R25") (pin "1") (pinfunction "1_1") (pintype "passive"))
      (node (ref "U$5") (pin "15") (pinfunction "SHPHLD_15") (pintype "bidirectional"))
    )
    (net (code "41") (name "Net-(U$5-SW1)") (class "Default")
      (node (ref "U$2") (pin "1") (pinfunction "1_1") (pintype "passive"))
      (node (ref "U$5") (pin "3") (pinfunction "SW1_3") (pintype "bidirectional"))
    )
    (net (code "42") (name "Net-(U$5-SW2)") (class "Default")
      (node (ref "U$3") (pin "1") (pinfunction "1_1") (pintype "passive"))
      (node (ref "U$5") (pin "5") (pinfunction "SW2_5") (pintype "bidirectional"))
    )
    (net (code "43") (name "Net-(U$5-VBAT)") (class "Default")
      (node (ref "BAT+1") (pin "TP") (pinfunction "TP_TP") (pintype "input"))
      (node (ref "C19") (pin "1") (pinfunction "1_1") (pintype "passive"))
      (node (ref "U$5") (pin "19") (pinfunction "VBAT_19") (pintype "bidirectional"))
    )
    (net (code "44") (name "Net-(U$5-VSET1)") (class "Default")
      (node (ref "R17") (pin "2") (pinfunction "2_2") (pintype "passive"))
      (node (ref "U$5") (pin "17") (pinfunction "VSET1_17") (pintype "bidirectional"))
    )
    (net (code "45") (name "Net-(U$5-VSET2)") (class "Default")
      (node (ref "R21") (pin "2") (pinfunction "2_2") (pintype "passive"))
      (node (ref "U$5") (pin "16") (pinfunction "VSET2_16") (pintype "bidirectional"))
    )
    (net (code "46") (name "Net-(U$22-LEDK1)") (class "Default")
      (node (ref "R5") (pin "2") (pinfunction "2_2") (pintype "passive"))
      (node (ref "U$22") (pin "11") (pinfunction "LEDK2_11") (pintype "bidirectional"))
      (node (ref "U$22") (pin "12") (pinfunction "LEDK1_12") (pintype "bidirectional"))
    )
    (net (code "47") (name "Net-(U$35-VCC)") (class "Default")
      (node (ref "C24") (pin "1") (pinfunction "1_1") (pintype "passive"))
      (node (ref "C25") (pin "1") (pinfunction "1_1") (pintype "passive"))
      (node (ref "C7") (pin "1") (pinfunction "1_1") (pintype "passive"))
      (node (ref "JMP4") (pin "2") (pinfunction "2_2") (pintype "passive"))
      (node (ref "U$35") (pin "8") (pinfunction "VCC_8") (pintype "bidirectional"))
    )
    (net (code "48") (name "Net-(U2-CLKOE)") (class "Default")
      (node (ref "R18") (pin "1") (pinfunction "1_1") (pintype "passive"))
      (node (ref "R20") (pin "2") (pinfunction "2_2") (pintype "passive"))
      (node (ref "U2") (pin "3") (pinfunction "CLKOE_3") (pintype "input"))
    )
    (net (code "49") (name "Net-(U4-SEL)") (class "Default")
      (node (ref "R13") (pin "2") (pinfunction "2_2") (pintype "passive"))
      (node (ref "R6") (pin "2") (pinfunction "2_2") (pintype "passive"))
      (node (ref "U4") (pin "15") (pinfunction "SEL_15") (pintype "passive"))
    )
    (net (code "50") (name "Net-(U4-~{EN})") (class "Default")
      (node (ref "JMP1") (pin "2") (pinfunction "2_2") (pintype "passive"))
      (node (ref "U4") (pin "13") (pinfunction "~{EN}_13") (pintype "passive"))
    )
    (net (code "51") (name "PPG_POWER") (class "Default")
      (node (ref "J4") (pin "1") (pinfunction "1_1") (pintype "passive"))
      (node (ref "J4") (pin "3") (pinfunction "3_3") (pintype "passive"))
      (node (ref "Q2") (pin "3") (pinfunction "D_3") (pintype "passive"))
    )
    (net (code "52") (name "QSPI-0") (class "Default")
      (node (ref "MDBT1") (pin "21") (pinfunction "P0.13/QSPI0_21") (pintype "bidirectional"))
      (node (ref "U$35") (pin "5") (pinfunction "DI(IO0)_5") (pintype "bidirectional"))
    )
    (net (code "53") (name "QSPI-1") (class "Default")
      (node (ref "MDBT1") (pin "27") (pinfunction "P0.14/QSPI1_27") (pintype "bidirectional"))
      (node (ref "U$35") (pin "2") (pinfunction "DO(IO1)_2") (pintype "bidirectional"))
    )
    (net (code "54") (name "QSPI-2") (class "Default")
      (node (ref "MDBT1") (pin "23") (pinfunction "P0.15/QSPI2_23") (pintype "bidirectional"))
      (node (ref "U$35") (pin "3") (pinfunction "WP(IO2)_3") (pintype "bidirectional"))
    )
    (net (code "55") (name "QSPI-3") (class "Default")
      (node (ref "MDBT1") (pin "28") (pinfunction "P0.16/QSPI3_28") (pintype "bidirectional"))
      (node (ref "U$35") (pin "7") (pinfunction "/HOLD(IO3)_7") (pintype "bidirectional"))
    )
    (net (code "56") (name "QSPI-CLK") (class "Default")
      (node (ref "MDBT1") (pin "26") (pinfunction "P0.17/QSPI_SCK_26") (pintype "bidirectional"))
      (node (ref "U$35") (pin "6") (pinfunction "CLK_6") (pintype "bidirectional"))
    )
    (net (code "57") (name "QSPI-CS") (class "Default")
      (node (ref "MDBT1") (pin "16") (pinfunction "P0.18/QSPI_CSN_16") (pintype "bidirectional"))
      (node (ref "U$35") (pin "1") (pinfunction "/CS_1") (pintype "bidirectional"))
    )
    (net (code "58") (name "RESET1") (class "Default")
      (node (ref "MDBT1") (pin "6") (pinfunction "RESET_6") (pintype "bidirectional"))
      (node (ref "P1") (pin "TP") (pinfunction "TP_TP") (pintype "input"))
    )
    (net (code "59") (name "RTC_INT") (class "Default")
      (node (ref "MDBT1") (pin "35") (pinfunction "P0.06/AIN2_35") (pintype "bidirectional"))
      (node (ref "R12") (pin "1") (pinfunction "1_1") (pintype "passive"))
      (node (ref "U2") (pin "4") (pinfunction "~{INT}_4") (pintype "output"))
    )
    (net (code "60") (name "SBU") (class "Default")
      (node (ref "D8") (pin "C") (pinfunction "C_C") (pintype "passive"))
      (node (ref "R2") (pin "2") (pinfunction "2_2") (pintype "passive"))
      (node (ref "R4") (pin "2") (pinfunction "2_2") (pintype "passive"))
    )
    (net (code "61") (name "SDO") (class "Default")
      (node (ref "U$22") (pin "6") (pinfunction "SDO_6") (pintype "bidirectional"))
    )
    (net (code "62") (name "SENSOR_BRD_SUPPLY") (class "Default")
      (node (ref "C20") (pin "1") (pinfunction "1_1") (pintype "passive"))
      (node (ref "C21") (pin "1") (pinfunction "1_1") (pintype "passive"))
      (node (ref "J3") (pin "1") (pinfunction "1_1") (pintype "passive"))
      (node (ref "J3") (pin "3") (pinfunction "3_3") (pintype "passive"))
      (node (ref "J3") (pin "5") (pinfunction "5_5") (pintype "passive"))
      (node (ref "J4") (pin "5") (pinfunction "5_5") (pintype "passive"))
      (node (ref "J4") (pin "7") (pinfunction "7_7") (pintype "passive"))
      (node (ref "J4") (pin "9") (pinfunction "9_9") (pintype "passive"))
      (node (ref "U$5") (pin "29") (pinfunction "LSOUT1/VOUTLDO1_29") (pintype "bidirectional"))
    )
    (net (code "63") (name "SEN_MFIO") (class "Default")
      (node (ref "J3") (pin "16") (pinfunction "16_16") (pintype "passive"))
      (node (ref "MDBT1") (pin "63") (pinfunction "P1.07_63") (pintype "bidirectional"))
    )
    (net (code "64") (name "SEN_MISO") (class "Default")
      (node (ref "J3") (pin "15") (pinfunction "15_15") (pintype "passive"))
      (node (ref "MDBT1") (pin "18") (pinfunction "P0.10/HSPI_MISO_18") (pintype "bidirectional"))
    )
    (net (code "65") (name "SEN_MOSI") (class "Default")
      (node (ref "J3") (pin "8") (pinfunction "8_8") (pintype "passive"))
      (node (ref "MDBT1") (pin "19") (pinfunction "P0.09/HSPI_MOSI_19") (pintype "bidirectional"))
    )
    (net (code "66") (name "SEN_RST") (class "Default")
      (node (ref "J3") (pin "19") (pinfunction "19_19") (pintype "passive"))
      (node (ref "MDBT1") (pin "10") (pinfunction "P1.06_10") (pintype "bidirectional"))
    )
    (net (code "67") (name "SEN_SCK") (class "Default")
      (node (ref "J3") (pin "4") (pinfunction "4_4") (pintype "passive"))
      (node (ref "MDBT1") (pin "29") (pinfunction "P0.08/HSPI_SCK_29") (pintype "bidirectional"))
    )
    (net (code "68") (name "SEN_SCL") (class "Default")
      (node (ref "J3") (pin "18") (pinfunction "18_18") (pintype "passive"))
      (node (ref "MDBT1") (pin "9") (pinfunction "P0.25/AIN4_9") (pintype "bidirectional"))
      (node (ref "R33") (pin "2") (pinfunction "2_2") (pintype "passive"))
      (node (ref "U$5") (pin "14") (pinfunction "SCL_14") (pintype "bidirectional"))
      (node (ref "U2") (pin "7") (pinfunction "SCL_7") (pintype "input"))
      (node (ref "U3") (pin "13") (pinfunction "SCL_13") (pintype "bidirectional"))
    )
    (net (code "69") (name "SEN_SDA") (class "Default")
      (node (ref "J3") (pin "17") (pinfunction "17_17") (pintype "passive"))
      (node (ref "MDBT1") (pin "8") (pinfunction "P0.24_8") (pintype "bidirectional"))
      (node (ref "R30") (pin "2") (pinfunction "2_2") (pintype "passive"))
      (node (ref "U$5") (pin "13") (pinfunction "SDA_13") (pintype "bidirectional"))
      (node (ref "U2") (pin "8") (pinfunction "SDA_8") (pintype "bidirectional"))
      (node (ref "U3") (pin "14") (pinfunction "SDA_14") (pintype "bidirectional"))
    )
    (net (code "70") (name "SHPHLD") (class "Default")
      (node (ref "JMP3") (pin "3") (pinfunction "3_3") (pintype "passive"))
      (node (ref "R25") (pin "2") (pinfunction "2_2") (pintype "passive"))
    )
    (net (code "71") (name "SW1") (class "Default")
      (node (ref "JMP2") (pin "3") (pinfunction "3_3") (pintype "passive"))
      (node (ref "MDBT1") (pin "39") (pinfunction "P0.05/AIN1_39") (pintype "bidirectional"))
    )
    (net (code "72") (name "SW3") (class "Default")
      (node (ref "JMP3") (pin "1") (pinfunction "1_1") (pintype "passive"))
      (node (ref "MDBT1") (pin "30") (pinfunction "P0.03/NFC2_30") (pintype "bidirectional"))
    )
    (net (code "73") (name "SWCLK1") (class "Default")
      (node (ref "J1") (pin "3") (pinfunction "3_3") (pintype "passive"))
      (node (ref "MDBT1") (pin "2") (pinfunction "SWDCLK_2") (pintype "bidirectional"))
      (node (ref "U4") (pin "4") (pinfunction "S2B_4") (pintype "bidirectional"))
    )
    (net (code "74") (name "SWDIO1") (class "Default")
      (node (ref "J1") (pin "4") (pinfunction "4_4") (pintype "passive"))
      (node (ref "MDBT1") (pin "4") (pinfunction "SWDIO_4") (pintype "bidirectional"))
      (node (ref "U4") (pin "1") (pinfunction "S1B_1") (pintype "bidirectional"))
    )
    (net (code "75") (name "SW_D1") (class "Default")
      (node (ref "D11") (pin "2") (pinfunction "2_2") (pintype "bidirectional"))
      (node (ref "J2") (pin "A2") (pinfunction "SSTXP1_A2") (pintype "bidirectional"))
      (node (ref "J2") (pin "B2") (pinfunction "SSTXP2_B2") (pintype "bidirectional"))
      (node (ref "U4") (pin "2") (pinfunction "D1_2") (pintype "bidirectional"))
    )
    (net (code "76") (name "SW_D2") (class "Default")
      (node (ref "D1") (pin "2") (pinfunction "2_2") (pintype "bidirectional"))
      (node (ref "J2") (pin "A3") (pinfunction "SSTXN1_A3") (pintype "bidirectional"))
      (node (ref "J2") (pin "B3") (pinfunction "SSTXN2_B3") (pintype "bidirectional"))
      (node (ref "U4") (pin "5") (pinfunction "D2_5") (pintype "bidirectional"))
    )
    (net (code "77") (name "SW_D3") (class "Default")
      (node (ref "D6") (pin "2") (pinfunction "2_2") (pintype "bidirectional"))
      (node (ref "J2") (pin "A11") (pinfunction "SSRXP2_A11") (pintype "bidirectional"))
      (node (ref "J2") (pin "B11") (pinfunction "SSRXP1_B11") (pintype "bidirectional"))
      (node (ref "U4") (pin "7") (pinfunction "D3_7") (pintype "bidirectional"))
    )
    (net (code "78") (name "SW_D4") (class "Default")
      (node (ref "D5") (pin "2") (pinfunction "2_2") (pintype "bidirectional"))
      (node (ref "J2") (pin "A10") (pinfunction "SSRXN2_A10") (pintype "bidirectional"))
      (node (ref "J2") (pin "B10") (pinfunction "SSRXN1_B10") (pintype "bidirectional"))
      (node (ref "U4") (pin "10") (pinfunction "D4_10") (pintype "bidirectional"))
    )
    (net (code "79") (name "S_INT") (class "Default")
      (node (ref "J4") (pin "8") (pinfunction "8_8") (pintype "passive"))
      (node (ref "U4") (pin "9") (pinfunction "S3A_9") (pintype "bidirectional"))
    )
    (net (code "80") (name "S_SCL") (class "Default")
      (node (ref "J4") (pin "6") (pinfunction "6_6") (pintype "passive"))
      (node (ref "U4") (pin "3") (pinfunction "S2A_3") (pintype "bidirectional"))
    )
    (net (code "81") (name "S_SDA") (class "Default")
      (node (ref "J4") (pin "4") (pinfunction "4_4") (pintype "passive"))
      (node (ref "U4") (pin "16") (pinfunction "S1A_16") (pintype "bidirectional"))
    )
    (net (code "82") (name "TFT_BL") (class "Default")
      (node (ref "MDBT1") (pin "22") (pinfunction "P1.05_22") (pintype "bidirectional"))
      (node (ref "R1") (pin "2") (pinfunction "2_2") (pintype "passive"))
    )
    (net (code "83") (name "TFT_CS") (class "Default")
      (node (ref "MDBT1") (pin "11") (pinfunction "P1.04_11") (pintype "bidirectional"))
      (node (ref "U$22") (pin "4") (pinfunction "CSX_4") (pintype "bidirectional"))
    )
    (net (code "84") (name "TFT_DC") (class "Default")
      (node (ref "MDBT1") (pin "43") (pinfunction "P1.01_43") (pintype "bidirectional"))
      (node (ref "U$22") (pin "8") (pinfunction "WRX/RS_8") (pintype "bidirectional"))
    )
    (net (code "85") (name "TFT_MOSI") (class "Default")
      (node (ref "MDBT1") (pin "51") (pinfunction "P1.13_51") (pintype "bidirectional"))
      (node (ref "U$22") (pin "7") (pinfunction "SDA_7") (pintype "bidirectional"))
    )
    (net (code "86") (name "TFT_RST") (class "Default")
      (node (ref "MDBT1") (pin "65") (pinfunction "P0.29_65") (pintype "bidirectional"))
      (node (ref "U$22") (pin "3") (pinfunction "RESET_3") (pintype "bidirectional"))
    )
    (net (code "87") (name "TFT_SCK") (class "Default")
      (node (ref "MDBT1") (pin "47") (pinfunction "P1.15_47") (pintype "bidirectional"))
      (node (ref "U$22") (pin "5") (pinfunction "DCX/SCL_5") (pintype "bidirectional"))
    )
    (net (code "88") (name "TP_INT") (class "Default")
      (node (ref "MDBT1") (pin "7") (pinfunction "P0.26/AIN5_7") (pintype "bidirectional"))
      (node (ref "U$22") (pin "16") (pinfunction "TP_INT_16") (pintype "bidirectional"))
    )
    (net (code "89") (name "TP_RST") (class "Default")
      (node (ref "MDBT1") (pin "5") (pinfunction "P0.27/AIN6_5") (pintype "bidirectional"))
      (node (ref "U$22") (pin "19") (pinfunction "TP_RST_19") (pintype "bidirectional"))
    )
    (net (code "90") (name "TP_SCL") (class "Default")
      (node (ref "MDBT1") (pin "31") (pinfunction "P1.03/TWI_31") (pintype "bidirectional"))
      (node (ref "R9") (pin "2") (pinfunction "2_2") (pintype "passive"))
      (node (ref "U$22") (pin "17") (pinfunction "TP_SCL_17") (pintype "bidirectional"))
    )
    (net (code "91") (name "TP_SDA") (class "Default")
      (node (ref "MDBT1") (pin "33") (pinfunction "P1.02/TWI_33") (pintype "bidirectional"))
      (node (ref "R11") (pin "2") (pinfunction "2_2") (pintype "passive"))
      (node (ref "U$22") (pin "18") (pinfunction "TP_SDA_18") (pintype "bidirectional"))
    )
    (net (code "92") (name "UART_TX") (class "Default")
      (node (ref "J1") (pin "2") (pinfunction "2_2") (pintype "power_in"))
      (node (ref "MDBT1") (pin "13") (pinfunction "P0.20_13") (pintype "bidirectional"))
      (node (ref "TX") (pin "TP") (pinfunction "TP_TP") (pintype "input"))
      (node (ref "U4") (pin "8") (pinfunction "S3B_8") (pintype "bidirectional"))
    )
    (net (code "93") (name "USB_D+") (class "Default")
      (node (ref "MDBT1") (pin "46") (pinfunction "D+_46") (pintype "bidirectional"))
      (node (ref "R31") (pin "2") (pinfunction "2_2") (pintype "passive"))
    )
    (net (code "94") (name "USB_D-") (class "Default")
      (node (ref "MDBT1") (pin "48") (pinfunction "D-_48") (pintype "bidirectional"))
      (node (ref "R32") (pin "2") (pinfunction "2_2") (pintype "passive"))
    )
    (net (code "95") (name "VBUS") (class "Default")
      (node (ref "MDBT1") (pin "44") (pinfunction "VBUS_44") (pintype "bidirectional"))
      (node (ref "U$5") (pin "22") (pinfunction "VBUSOUT_22") (pintype "bidirectional"))
    )
    (net (code "96") (name "VCC") (class "Default")
      (node (ref "C1") (pin "1") (pinfunction "1_1") (pintype "passive"))
      (node (ref "C3") (pin "1") (pinfunction "1_1") (pintype "passive"))
      (node (ref "C6") (pin "1") (pinfunction "1_1") (pintype "passive"))
      (node (ref "U$5") (pin "20") (pinfunction "VSYS_20") (pintype "bidirectional"))
      (node (ref "U$5") (pin "4") (pinfunction "PVDD_4") (pintype "bidirectional"))
    )
    (net (code "97") (name "VUSB2") (class "Default")
      (node (ref "C18") (pin "1") (pinfunction "1_1") (pintype "passive"))
      (node (ref "C5") (pin "1") (pinfunction "1_1") (pintype "passive"))
      (node (ref "J2") (pin "A4") (pinfunction "VBUS_A_A4") (pintype "power_in"))
      (node (ref "J2") (pin "A9") (pinfunction "VBUS_A_A9") (pintype "power_in"))
      (node (ref "J2") (pin "B4") (pinfunction "VBUS_B_B4") (pintype "power_in"))
      (node (ref "J2") (pin "B9") (pinfunction "VBUS_B_B9") (pintype "power_in"))
      (node (ref "Q2") (pin "1") (pinfunction "G_1") (pintype "passive"))
      (node (ref "R15") (pin "2") (pinfunction "2_2") (pintype "passive"))
      (node (ref "R6") (pin "1") (pinfunction "1_1") (pintype "passive"))
      (node (ref "U$5") (pin "21") (pinfunction "VBUS_21") (pintype "bidirectional"))
    )
    (net (code "98") (name "W_MFIO") (class "Default")
      (node (ref "J3") (pin "12") (pinfunction "12_12") (pintype "passive"))
      (node (ref "MDBT1") (pin "60") (pinfunction "P0.28/AIN7_60") (pintype "bidirectional"))
    )
    (net (code "99") (name "unconnected-(J3-Pad6)") (class "Default")
      (node (ref "J3") (pin "6") (pinfunction "6_6") (pintype "passive"))
    )
    (net (code "100") (name "unconnected-(J3-Pad7)") (class "Default")
      (node (ref "J3") (pin "7") (pinfunction "7_7") (pintype "passive"))
    )
    (net (code "101") (name "unconnected-(J3-Pad10)") (class "Default")
      (node (ref "J3") (pin "10") (pinfunction "10_10") (pintype "passive"))
    )
    (net (code "102") (name "unconnected-(J3-Pad13)") (class "Default")
      (node (ref "J3") (pin "13") (pinfunction "13_13") (pintype "passive"))
    )
    (net (code "103") (name "unconnected-(J4-Pad10)") (class "Default")
      (node (ref "J4") (pin "10") (pinfunction "10_10") (pintype "passive"))
    )
    (net (code "104") (name "unconnected-(J4-Pad11)") (class "Default")
      (node (ref "J4") (pin "11") (pinfunction "11_11") (pintype "passive"))
    )
    (net (code "105") (name "unconnected-(J4-Pad12)") (class "Default")
      (node (ref "J4") (pin "12") (pinfunction "12_12") (pintype "passive"))
    )
    (net (code "106") (name "unconnected-(J4-Pad13)") (class "Default")
      (node (ref "J4") (pin "13") (pinfunction "13_13") (pintype "passive"))
    )
    (net (code "107") (name "unconnected-(J4-Pad14)") (class "Default")
      (node (ref "J4") (pin "14") (pinfunction "14_14") (pintype "passive"))
    )
    (net (code "108") (name "unconnected-(MDBT1-P0.04{slash}AIN0-Pad37)") (class "Default")
      (node (ref "MDBT1") (pin "37") (pinfunction "P0.04/AIN0_37") (pintype "bidirectional"))
    )
    (net (code "109") (name "unconnected-(MDBT1-P0.11{slash}HSPI_CSN-Pad17)") (class "Default")
      (node (ref "MDBT1") (pin "17") (pinfunction "P0.11/HSPI_CSN_17") (pintype "bidirectional"))
    )
    (net (code "110") (name "unconnected-(MDBT1-P0.12{slash}HSPI_DCX-Pad15)") (class "Default")
      (node (ref "MDBT1") (pin "15") (pinfunction "P0.12/HSPI_DCX_15") (pintype "bidirectional"))
    )
    (net (code "111") (name "unconnected-(MDBT1-P0.22-Pad25)") (class "Default")
      (node (ref "MDBT1") (pin "25") (pinfunction "P0.22_25") (pintype "bidirectional"))
    )
    (net (code "112") (name "unconnected-(MDBT1-P0.23-Pad62)") (class "Default")
      (node (ref "MDBT1") (pin "62") (pinfunction "P0.23_62") (pintype "bidirectional"))
    )
    (net (code "113") (name "unconnected-(MDBT1-P0.30-Pad57)") (class "Default")
      (node (ref "MDBT1") (pin "57") (pinfunction "P0.30_57") (pintype "bidirectional"))
    )
    (net (code "114") (name "unconnected-(MDBT1-P0.31-Pad56)") (class "Default")
      (node (ref "MDBT1") (pin "56") (pinfunction "P0.31_56") (pintype "bidirectional"))
    )
    (net (code "115") (name "unconnected-(MDBT1-P1.00-Pad45)") (class "Default")
      (node (ref "MDBT1") (pin "45") (pinfunction "P1.00_45") (pintype "bidirectional"))
    )
    (net (code "116") (name "unconnected-(MDBT1-P1.12-Pad53)") (class "Default")
      (node (ref "MDBT1") (pin "53") (pinfunction "P1.12_53") (pintype "bidirectional"))
    )
    (net (code "117") (name "unconnected-(MDBT1-P1.14-Pad49)") (class "Default")
      (node (ref "MDBT1") (pin "49") (pinfunction "P1.14_49") (pintype "bidirectional"))
    )
    (net (code "118") (name "unconnected-(U$5-GPIO3-Pad10)") (class "Default")
      (node (ref "U$5") (pin "10") (pinfunction "GPIO3_10") (pintype "bidirectional"))
    )
    (net (code "119") (name "unconnected-(U$5-GPIO4-Pad11)") (class "Default")
      (node (ref "U$5") (pin "11") (pinfunction "GPIO4_11") (pintype "bidirectional"))
    )
    (net (code "120") (name "unconnected-(U$5-LED0-Pad25)") (class "Default")
      (node (ref "U$5") (pin "25") (pinfunction "LED0_25") (pintype "bidirectional"))
    )
    (net (code "121") (name "unconnected-(U$5-LED1-Pad26)") (class "Default")
      (node (ref "U$5") (pin "26") (pinfunction "LED1_26") (pintype "bidirectional"))
    )
    (net (code "122") (name "unconnected-(U$5-LED2-Pad27)") (class "Default")
      (node (ref "U$5") (pin "27") (pinfunction "LED2_27") (pintype "bidirectional"))
    )
    (net (code "123") (name "unconnected-(U$5-LSIN2{slash}VINLDO2-Pad30)") (class "Default")
      (node (ref "U$5") (pin "30") (pinfunction "LSIN2/VINLDO2_30") (pintype "bidirectional"))
    )
    (net (code "124") (name "unconnected-(U$5-LSOUT2{slash}VOUTLDO2-Pad31)") (class "Default")
      (node (ref "U$5") (pin "31") (pinfunction "LSOUT2/VOUTLDO2_31") (pintype "bidirectional"))
    )
    (net (code "125") (name "unconnected-(U$17-0-Pad1)") (class "Default")
      (node (ref "U$17") (pin "1") (pinfunction "0_1") (pintype "passive"))
    )
    (net (code "126") (name "unconnected-(U$17-1-Pad4)") (class "Default")
      (node (ref "U$17") (pin "4") (pinfunction "1_4") (pintype "passive"))
    )
    (net (code "127") (name "unconnected-(U$22-NC-Pad15)") (class "Default")
      (node (ref "U$22") (pin "15") (pinfunction "NC_15") (pintype "bidirectional"))
    )
    (net (code "128") (name "unconnected-(U$24-0-Pad1)") (class "Default")
      (node (ref "U$24") (pin "1") (pinfunction "0_1") (pintype "passive"))
    )
    (net (code "129") (name "unconnected-(U$24-1-Pad4)") (class "Default")
      (node (ref "U$24") (pin "4") (pinfunction "1_4") (pintype "passive"))
    )
    (net (code "130") (name "unconnected-(U2-CLKOUT-Pad6)") (class "Default")
      (node (ref "U2") (pin "6") (pinfunction "CLKOUT_6") (pintype "output"))
    )
    (net (code "131") (name "unconnected-(U2-NC-Pad1)") (class "Default")
      (node (ref "U2") (pin "1") (pinfunction "NC_1") (pintype "no_connect"))
    )
    (net (code "132") (name "unconnected-(U3-INT2-Pad9)") (class "Default")
      (node (ref "U3") (pin "9") (pinfunction "INT2_9") (pintype "bidirectional"))
    )
    (net (code "133") (name "unconnected-(U3-NC-Pad11)") (class "Default")
      (node (ref "U3") (pin "11") (pinfunction "NC_11") (pintype "bidirectional"))
    )
    (net (code "134") (name "unconnected-(U3-OCS-Pad10)") (class "Default")
      (node (ref "U3") (pin "10") (pinfunction "OCS_10") (pintype "bidirectional"))
    )
    (net (code "135") (name "unconnected-(U4-S4A-Pad12)") (class "Default")
      (node (ref "U4") (pin "12") (pinfunction "S4A_12") (pintype "bidirectional"))
    )
    (net (code "136") (name "unconnected-(U4-S4B-Pad11)") (class "Default")
      (node (ref "U4") (pin "11") (pinfunction "S4B_11") (pintype "bidirectional"))
    )
  )
)
